# STorM32_NT_logger_v13.net
KiCad netlist of a schematic drawn in EAGLE
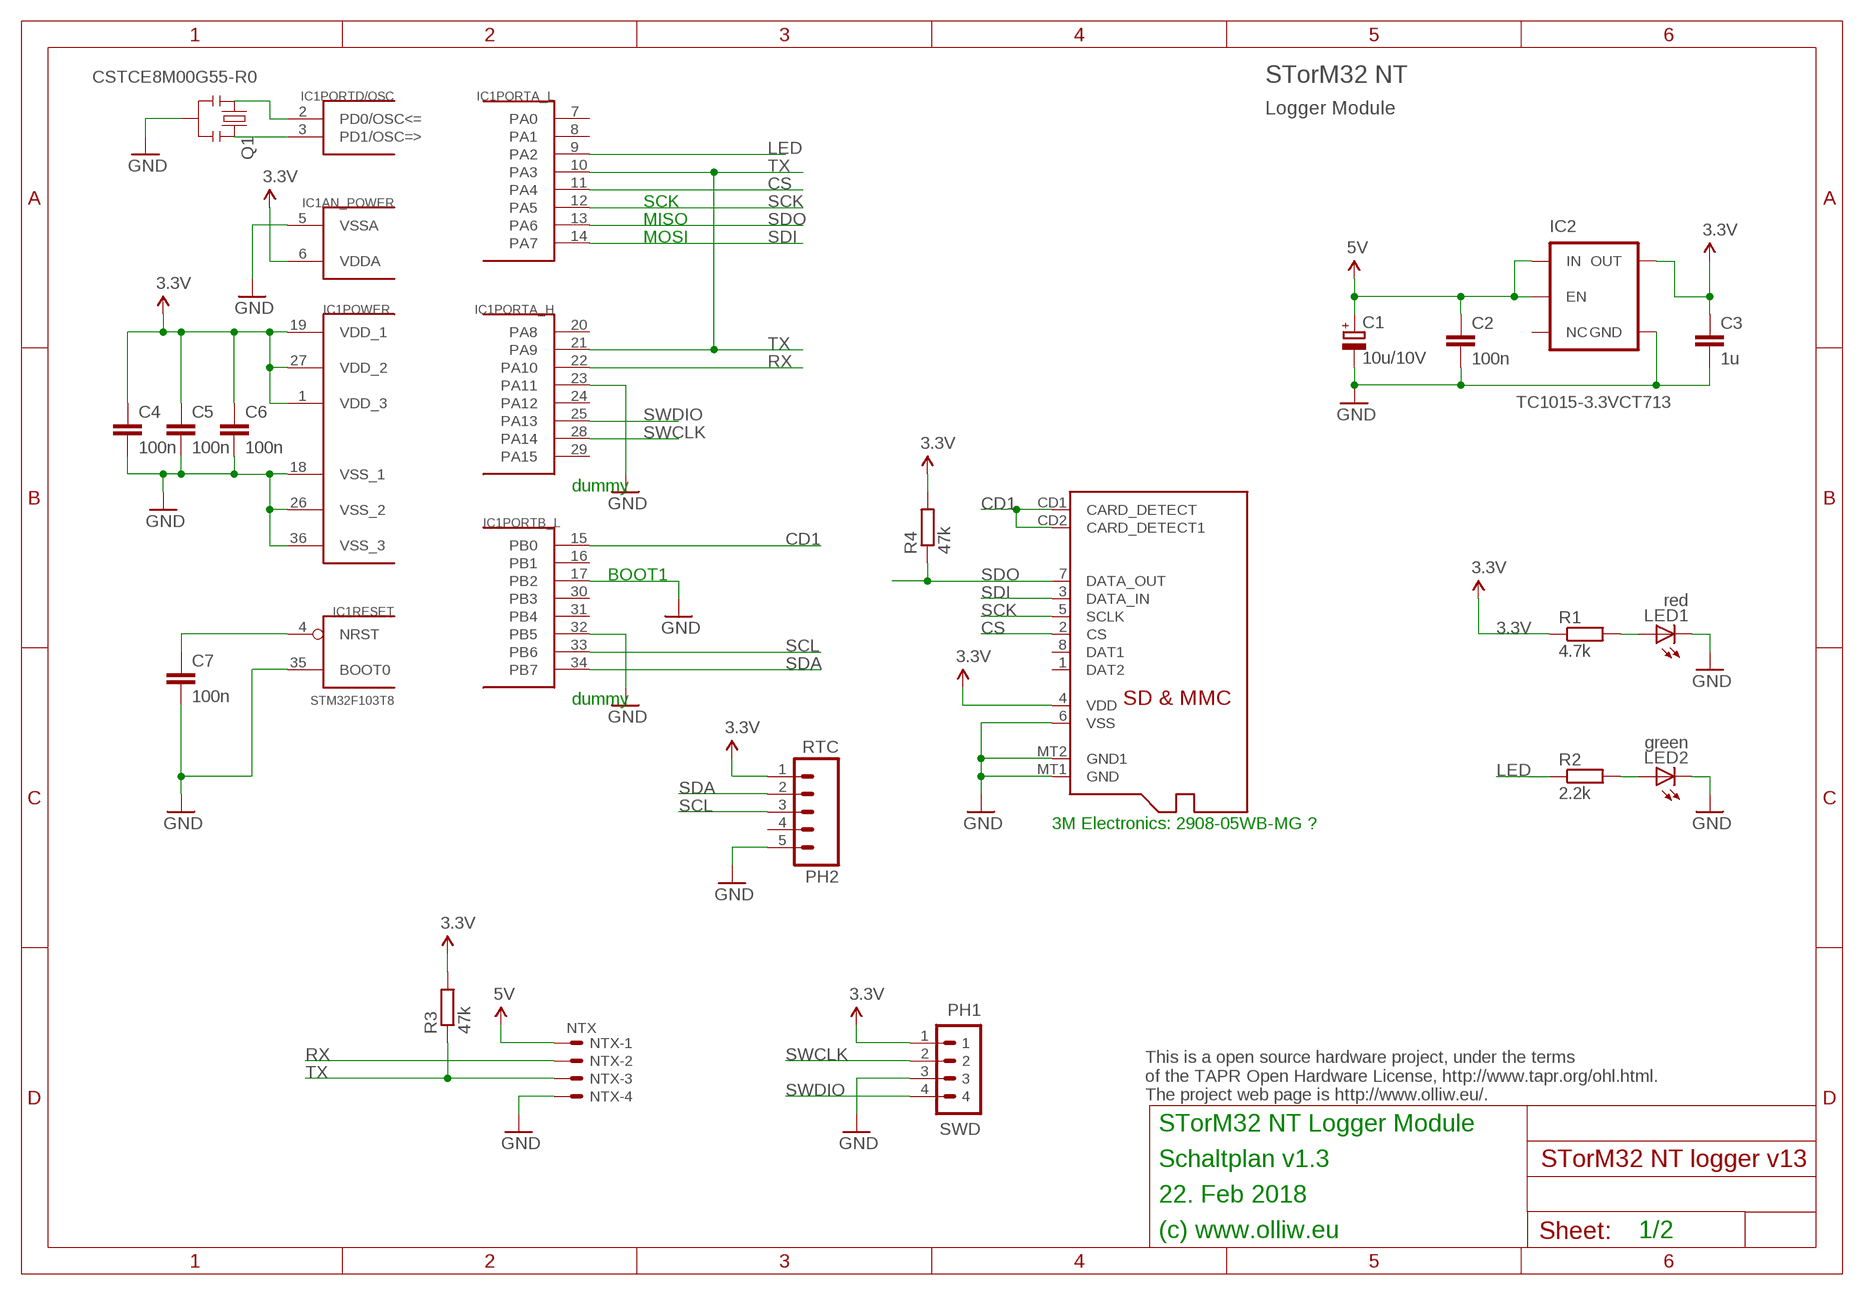
[diagram p0: schematic, sheet 1]

(export (version "E")
  (design (tool "Eeschema 10.0.6"))
  (components
    (comp (ref "C1")
      (value "10u/10V")
      (footprint "eagle-import:SMC_B")
      (libsource (lib "eagle-import") (part "CPOL-EUSMCB"))
    )
    (comp (ref "C2")
      (value "100n")
      (footprint "eagle-import:C0603")
      (libsource (lib "eagle-import") (part "C-EUC0603"))
    )
    (comp (ref "C3")
      (value "1u")
      (footprint "eagle-import:C0603")
      (libsource (lib "eagle-import") (part "C-EUC0603"))
    )
    (comp (ref "C4")
      (value "100n")
      (footprint "eagle-import:C0603")
      (libsource (lib "eagle-import") (part "C-EUC0603"))
    )
    (comp (ref "C5")
      (value "100n")
      (footprint "eagle-import:C0603")
      (libsource (lib "eagle-import") (part "C-EUC0603"))
    )
    (comp (ref "C6")
      (value "100n")
      (footprint "eagle-import:C0603")
      (libsource (lib "eagle-import") (part "C-EUC0603"))
    )
    (comp (ref "C7")
      (value "100n")
      (footprint "eagle-import:C0603")
      (libsource (lib "eagle-import") (part "C-EUC0603"))
    )
    (comp (ref "IC1")
      (value "STM32F103T8")
      (footprint "eagle-import:VFQFPN36")
      (libsource (lib "eagle-import") (part "STM32F10XTXU6"))
    )
    (comp (ref "IC2")
      (value "TC1015-3.3VCT713")
      (footprint "eagle-import:SOT23-5")
      (libsource (lib "eagle-import") (part "V_REG_TPS76433SOT23-5"))
    )
    (comp (ref "LED1")
      (value "red")
      (footprint "eagle-import:CHIPLED_0603")
      (libsource (lib "eagle-import") (part "LEDCHIPLED_0603"))
    )
    (comp (ref "LED2")
      (value "green")
      (footprint "eagle-import:CHIPLED_0603")
      (libsource (lib "eagle-import") (part "LEDCHIPLED_0603"))
    )
    (comp (ref "NTX")
      (value "NTX")
      (footprint "eagle-import:SM04B-SRSS-TB")
      (libsource (lib "eagle-import") (part "?M04B-SRSS-TBS"))
    )
    (comp (ref "PH1")
      (value "SWD")
      (footprint "eagle-import:4X1_1P27_OCT_BILEX")
      (libsource (lib "eagle-import") (part "P4X1_1P27-OCT_BILEX"))
    )
    (comp (ref "PH2")
      (value "RTC")
      (footprint "eagle-import:1X05")
      (libsource (lib "eagle-import") (part "M05PTH"))
    )
    (comp (ref "Q1")
      (value "CSTCE8M00G55-R0")
      (footprint "eagle-import:RESONATOR-SMD")
      (libsource (lib "eagle-import") (part "RESONATORSMD"))
    )
    (comp (ref "R1")
      (value "4.7k")
      (footprint "eagle-import:R0603")
      (libsource (lib "eagle-import") (part "R-EU_R0603"))
    )
    (comp (ref "R2")
      (value "2.2k")
      (footprint "eagle-import:R0603")
      (libsource (lib "eagle-import") (part "R-EU_R0603"))
    )
    (comp (ref "R3")
      (value "47k")
      (footprint "eagle-import:R0603")
      (libsource (lib "eagle-import") (part "R-EU_R0603"))
    )
    (comp (ref "R4")
      (value "47k")
      (footprint "eagle-import:R0603")
      (libsource (lib "eagle-import") (part "R-EU_R0603"))
    )
    (comp (ref "U1")
      (value "3M 2908-05WB-MG ??")
      (footprint "eagle-import:MICROSD")
      (libsource (lib "eagle-import") (part "MICROSD"))
    )
  )
  (nets
    (net (code "1") (name "/CD1") (class "Default")
      (node (ref "IC1") (pin "15") (pinfunction "PB0_15") (pintype "bidirectional"))
      (node (ref "U1") (pin "CD1") (pinfunction "CARD_DETECT_CD1") (pintype "passive"))
      (node (ref "U1") (pin "CD2") (pinfunction "CARD_DETECT1_CD2") (pintype "passive"))
    )
    (net (code "2") (name "/CS") (class "Default")
      (node (ref "IC1") (pin "11") (pinfunction "PA4_11") (pintype "bidirectional"))
      (node (ref "U1") (pin "2") (pinfunction "CS_2") (pintype "input"))
    )
    (net (code "3") (name "/LED") (class "Default")
      (node (ref "IC1") (pin "9") (pinfunction "PA2_9") (pintype "bidirectional"))
      (node (ref "R2") (pin "1") (pinfunction "1_1") (pintype "passive"))
    )
    (net (code "4") (name "/RX") (class "Default")
      (node (ref "IC1") (pin "22") (pinfunction "PA10_22") (pintype "bidirectional"))
      (node (ref "NTX") (pin "2") (pinfunction "S_2") (pintype "passive"))
    )
    (net (code "5") (name "/SCK") (class "Default")
      (node (ref "IC1") (pin "12") (pinfunction "PA5_12") (pintype "bidirectional"))
      (node (ref "U1") (pin "5") (pinfunction "SCLK_5") (pintype "input"))
    )
    (net (code "6") (name "/SCL") (class "Default")
      (node (ref "IC1") (pin "33") (pinfunction "PB6_33") (pintype "bidirectional"))
      (node (ref "PH2") (pin "3") (pinfunction "3_3") (pintype "passive"))
    )
    (net (code "7") (name "/SDA") (class "Default")
      (node (ref "IC1") (pin "34") (pinfunction "PB7_34") (pintype "bidirectional"))
      (node (ref "PH2") (pin "2") (pinfunction "2_2") (pintype "passive"))
    )
    (net (code "8") (name "/SDI") (class "Default")
      (node (ref "IC1") (pin "14") (pinfunction "PA7_14") (pintype "bidirectional"))
      (node (ref "U1") (pin "3") (pinfunction "DATA_IN_3") (pintype "input"))
    )
    (net (code "9") (name "/SDO") (class "Default")
      (node (ref "IC1") (pin "13") (pinfunction "PA6_13") (pintype "bidirectional"))
      (node (ref "R4") (pin "1") (pinfunction "1_1") (pintype "passive"))
      (node (ref "U1") (pin "7") (pinfunction "DATA_OUT_7") (pintype "output"))
    )
    (net (code "10") (name "/SWCLK") (class "Default")
      (node (ref "IC1") (pin "28") (pinfunction "PA14_28") (pintype "bidirectional"))
      (node (ref "PH1") (pin "2") (pinfunction "2_2") (pintype "passive"))
    )
    (net (code "11") (name "/SWDIO") (class "Default")
      (node (ref "IC1") (pin "25") (pinfunction "PA13_25") (pintype "bidirectional"))
      (node (ref "PH1") (pin "4") (pinfunction "4_4") (pintype "passive"))
    )
    (net (code "12") (name "/TX") (class "Default")
      (node (ref "IC1") (pin "10") (pinfunction "PA3_10") (pintype "bidirectional"))
      (node (ref "IC1") (pin "21") (pinfunction "PA9_21") (pintype "bidirectional"))
      (node (ref "NTX") (pin "3") (pinfunction "S_3") (pintype "passive"))
      (node (ref "R3") (pin "1") (pinfunction "1_1") (pintype "passive"))
    )
    (net (code "13") (name "3.3V") (class "Default")
      (node (ref "C3") (pin "1") (pinfunction "1_1") (pintype "passive"))
      (node (ref "C4") (pin "1") (pinfunction "1_1") (pintype "passive"))
      (node (ref "C5") (pin "1") (pinfunction "1_1") (pintype "passive"))
      (node (ref "C6") (pin "1") (pinfunction "1_1") (pintype "passive"))
      (node (ref "IC1") (pin "1") (pinfunction "VDD_3_1") (pintype "power_in"))
      (node (ref "IC1") (pin "19") (pinfunction "VDD_1_19") (pintype "power_in"))
      (node (ref "IC1") (pin "27") (pinfunction "VDD_2_27") (pintype "power_in"))
      (node (ref "IC1") (pin "6") (pinfunction "VDDA_6") (pintype "power_in"))
      (node (ref "IC2") (pin "5") (pinfunction "OUT_5") (pintype "passive"))
      (node (ref "PH1") (pin "1") (pinfunction "1_1") (pintype "passive"))
      (node (ref "PH2") (pin "1") (pinfunction "1_1") (pintype "passive"))
      (node (ref "R1") (pin "1") (pinfunction "1_1") (pintype "passive"))
      (node (ref "R3") (pin "2") (pinfunction "2_2") (pintype "passive"))
      (node (ref "R4") (pin "2") (pinfunction "2_2") (pintype "passive"))
      (node (ref "U1") (pin "4") (pinfunction "VDD_4") (pintype "power_in"))
    )
    (net (code "14") (name "5V") (class "Default")
      (node (ref "C1") (pin "+") (pinfunction "+_+") (pintype "passive"))
      (node (ref "C2") (pin "1") (pinfunction "1_1") (pintype "passive"))
      (node (ref "IC2") (pin "1") (pinfunction "IN_1") (pintype "input"))
      (node (ref "IC2") (pin "3") (pinfunction "EN_3") (pintype "input"))
      (node (ref "NTX") (pin "1") (pinfunction "S_1") (pintype "passive"))
    )
    (net (code "15") (name "GND") (class "Default")
      (node (ref "C1") (pin "-") (pinfunction "-_-") (pintype "passive"))
      (node (ref "C2") (pin "2") (pinfunction "2_2") (pintype "passive"))
      (node (ref "C3") (pin "2") (pinfunction "2_2") (pintype "passive"))
      (node (ref "C4") (pin "2") (pinfunction "2_2") (pintype "passive"))
      (node (ref "C5") (pin "2") (pinfunction "2_2") (pintype "passive"))
      (node (ref "C6") (pin "2") (pinfunction "2_2") (pintype "passive"))
      (node (ref "C7") (pin "2") (pinfunction "2_2") (pintype "passive"))
      (node (ref "IC1") (pin "17") (pinfunction "PB2_17") (pintype "bidirectional"))
      (node (ref "IC1") (pin "18") (pinfunction "VSS_1_18") (pintype "power_in"))
      (node (ref "IC1") (pin "23") (pinfunction "PA11_23") (pintype "bidirectional"))
      (node (ref "IC1") (pin "26") (pinfunction "VSS_2_26") (pintype "power_in"))
      (node (ref "IC1") (pin "32") (pinfunction "PB5_32") (pintype "bidirectional"))
      (node (ref "IC1") (pin "35") (pinfunction "BOOT0_35") (pintype "input"))
      (node (ref "IC1") (pin "36") (pinfunction "VSS_3_36") (pintype "power_in"))
      (node (ref "IC1") (pin "5") (pinfunction "VSSA_5") (pintype "power_in"))
      (node (ref "IC2") (pin "2") (pinfunction "GND_2") (pintype "input"))
      (node (ref "LED1") (pin "C") (pinfunction "C_C") (pintype "passive"))
      (node (ref "LED2") (pin "C") (pinfunction "C_C") (pintype "passive"))
      (node (ref "NTX") (pin "4") (pinfunction "S_4") (pintype "passive"))
      (node (ref "PH1") (pin "3") (pinfunction "3_3") (pintype "passive"))
      (node (ref "PH2") (pin "5") (pinfunction "5_5") (pintype "passive"))
      (node (ref "Q1") (pin "2") (pinfunction "2_2") (pintype "passive"))
      (node (ref "U1") (pin "6") (pinfunction "VSS_6") (pintype "power_in"))
      (node (ref "U1") (pin "MT1") (pinfunction "GND_MT1") (pintype "power_in"))
      (node (ref "U1") (pin "MT2") (pinfunction "GND1_MT2") (pintype "power_in"))
    )
    (net (code "16") (name "Net-(IC1E-PD0{slash}OSC<=)") (class "Default")
      (node (ref "IC1") (pin "2") (pinfunction "PD0/OSC<=_2") (pintype "bidirectional"))
      (node (ref "Q1") (pin "1") (pinfunction "1_1") (pintype "passive"))
    )
    (net (code "17") (name "Net-(IC1E-PD1{slash}OSC=>)") (class "Default")
      (node (ref "IC1") (pin "3") (pinfunction "PD1/OSC=>_3") (pintype "bidirectional"))
      (node (ref "Q1") (pin "3") (pinfunction "3_3") (pintype "passive"))
    )
    (net (code "18") (name "Net-(IC1G-NRST)") (class "Default")
      (node (ref "C7") (pin "1") (pinfunction "1_1") (pintype "passive"))
      (node (ref "IC1") (pin "4") (pinfunction "NRST_4") (pintype "input"))
    )
    (net (code "19") (name "Net-(LED1-PadA)") (class "Default")
      (node (ref "LED1") (pin "A") (pinfunction "A_A") (pintype "passive"))
      (node (ref "R1") (pin "2") (pinfunction "2_2") (pintype "passive"))
    )
    (net (code "20") (name "Net-(LED2-PadA)") (class "Default")
      (node (ref "LED2") (pin "A") (pinfunction "A_A") (pintype "passive"))
      (node (ref "R2") (pin "2") (pinfunction "2_2") (pintype "passive"))
    )
    (net (code "21") (name "unconnected-(IC1B-PA8-Pad20)") (class "Default")
      (node (ref "IC1") (pin "20") (pinfunction "PA8_20") (pintype "bidirectional"))
    )
    (net (code "22") (name "unconnected-(IC1B-PA12-Pad24)") (class "Default")
      (node (ref "IC1") (pin "24") (pinfunction "PA12_24") (pintype "bidirectional"))
    )
    (net (code "23") (name "unconnected-(IC1B-PA15-Pad29)") (class "Default")
      (node (ref "IC1") (pin "29") (pinfunction "PA15_29") (pintype "bidirectional"))
    )
    (net (code "24") (name "unconnected-(IC1C-PA0-Pad7)") (class "Default")
      (node (ref "IC1") (pin "7") (pinfunction "PA0_7") (pintype "bidirectional"))
    )
    (net (code "25") (name "unconnected-(IC1C-PA1-Pad8)") (class "Default")
      (node (ref "IC1") (pin "8") (pinfunction "PA1_8") (pintype "bidirectional"))
    )
    (net (code "26") (name "unconnected-(IC1D-PB1-Pad16)") (class "Default")
      (node (ref "IC1") (pin "16") (pinfunction "PB1_16") (pintype "bidirectional"))
    )
    (net (code "27") (name "unconnected-(IC1D-PB3-Pad30)") (class "Default")
      (node (ref "IC1") (pin "30") (pinfunction "PB3_30") (pintype "bidirectional"))
    )
    (net (code "28") (name "unconnected-(IC1D-PB4-Pad31)") (class "Default")
      (node (ref "IC1") (pin "31") (pinfunction "PB4_31") (pintype "bidirectional"))
    )
    (net (code "29") (name "unconnected-(IC2-NC-Pad4)") (class "Default")
      (node (ref "IC2") (pin "4") (pinfunction "NC_4") (pintype "input"))
    )
    (net (code "30") (name "unconnected-(PH2-Pad4)") (class "Default")
      (node (ref "PH2") (pin "4") (pinfunction "4_4") (pintype "passive"))
    )
    (net (code "31") (name "unconnected-(U1-DAT1-Pad8)") (class "Default")
      (node (ref "U1") (pin "8") (pinfunction "DAT1_8") (pintype "bidirectional"))
    )
    (net (code "32") (name "unconnected-(U1-DAT2-Pad1)") (class "Default")
      (node (ref "U1") (pin "1") (pinfunction "DAT2_1") (pintype "bidirectional"))
    )
  )
)
